# untitled.net
KiCad netlist of a schematic drawn in EAGLE
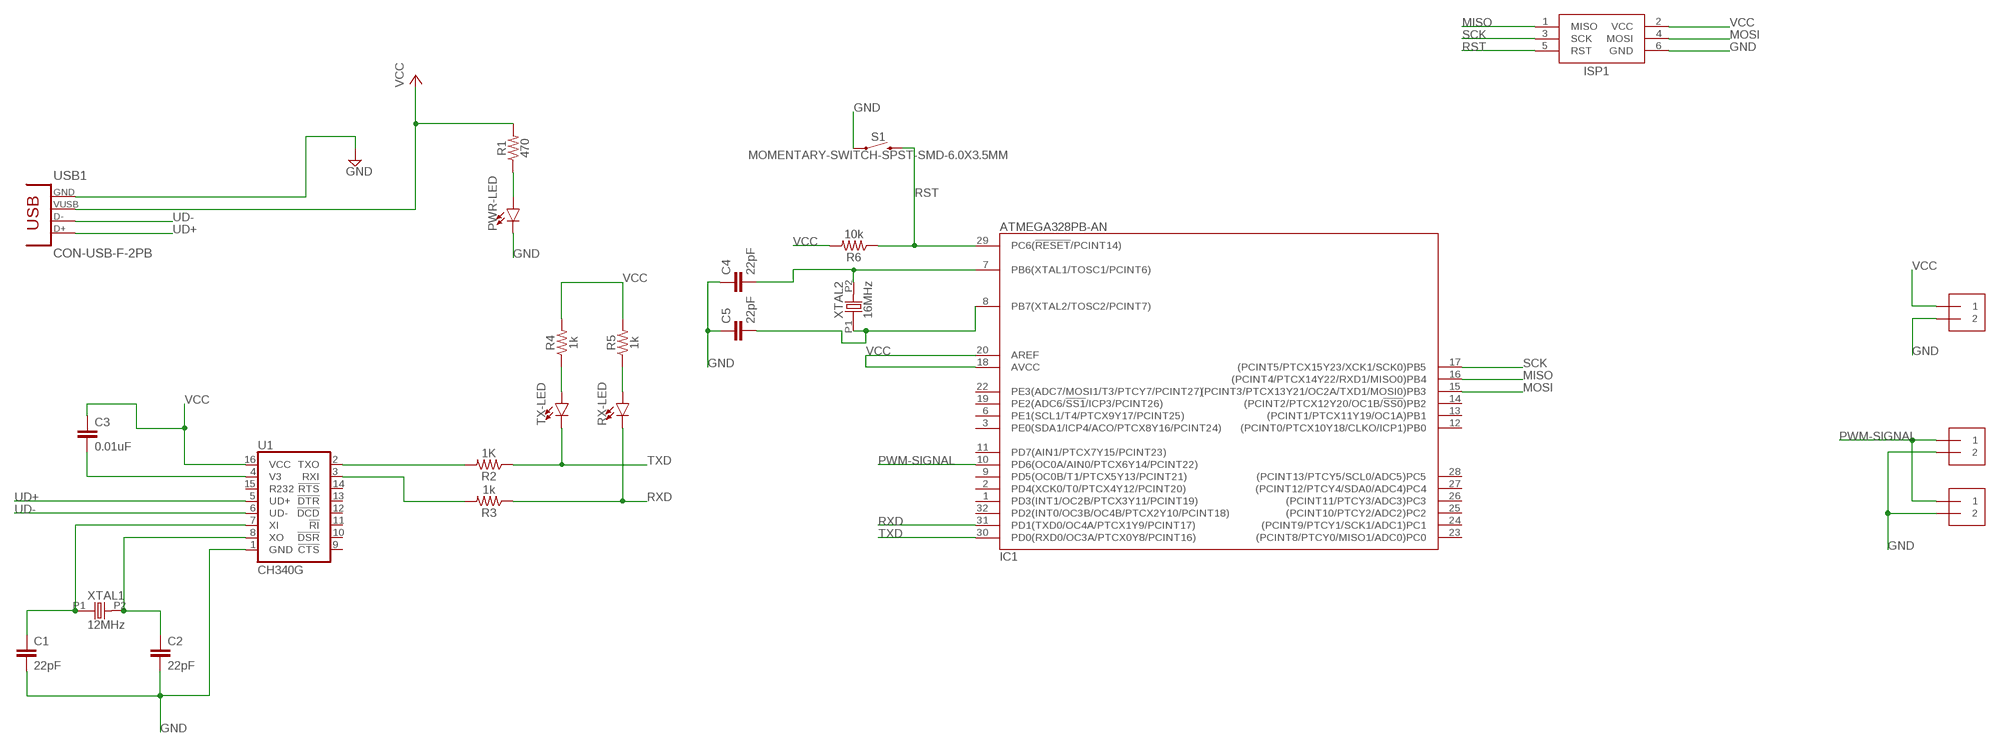
[diagram p0: schematic, sheet 1]

(export (version "E")
  (design (tool "Eeschema 10.0.6"))
  (components
    (comp (ref "5V/GND")
      (value "1X2-3.5MM")
      (footprint "eagle-import:1X2-3.5MM")
      (libsource (lib "eagle-import") (part "1X2-3.5MM"))
    )
    (comp (ref "C1")
      (value "22pF")
      (footprint "eagle-import:0603")
      (libsource (lib "eagle-import") (part "22PF-0603-50V-5%"))
    )
    (comp (ref "C2")
      (value "22pF")
      (footprint "eagle-import:0603")
      (libsource (lib "eagle-import") (part "22PF-0603-50V-5%"))
    )
    (comp (ref "C3")
      (value "0.01uF")
      (footprint "eagle-import:0603")
      (libsource (lib "eagle-import") (part "22PF-0603-50V-5%"))
    )
    (comp (ref "C4")
      (value "22pF")
      (footprint "eagle-import:0603")
      (libsource (lib "eagle-import") (part "22PF-0603-50V-5%"))
    )
    (comp (ref "C5")
      (value "22pF")
      (footprint "eagle-import:0603")
      (libsource (lib "eagle-import") (part "22PF-0603-50V-5%"))
    )
    (comp (ref "IC1")
      (value "ATMEGA328PB-AN")
      (footprint "eagle-import:QFP32_7X7_0.80")
      (libsource (lib "eagle-import") (part "ATMEGA328PB-AN"))
    )
    (comp (ref "ISP1")
      (value "AVRISP-6")
      (footprint "eagle-import:AVRISP")
      (libsource (lib "eagle-import") (part "AVRISP-6"))
    )
    (comp (ref "MOTOR-1")
      (value "1X2-3.5MM")
      (footprint "eagle-import:1X2-3.5MM")
      (libsource (lib "eagle-import") (part "1X2-3.5MM"))
    )
    (comp (ref "MOTOR-2")
      (value "1X2-3.5MM")
      (footprint "eagle-import:1X2-3.5MM")
      (libsource (lib "eagle-import") (part "1X2-3.5MM"))
    )
    (comp (ref "PWR-LED")
      (value "LED1206")
      (footprint "eagle-import:LED-1206")
      (libsource (lib "eagle-import") (part "LED1206"))
    )
    (comp (ref "R1")
      (value "470")
      (footprint "eagle-import:1206")
      (libsource (lib "eagle-import") (part "RESISTOR1206"))
    )
    (comp (ref "R2")
      (value "1K")
      (footprint "eagle-import:1206")
      (libsource (lib "eagle-import") (part "RESISTOR1206"))
    )
    (comp (ref "R3")
      (value "1k")
      (footprint "eagle-import:1206")
      (libsource (lib "eagle-import") (part "RESISTOR1206"))
    )
    (comp (ref "R4")
      (value "1k")
      (footprint "eagle-import:1206")
      (libsource (lib "eagle-import") (part "RESISTOR1206"))
    )
    (comp (ref "R5")
      (value "1k")
      (footprint "eagle-import:1206")
      (libsource (lib "eagle-import") (part "RESISTOR1206"))
    )
    (comp (ref "R6")
      (value "10k")
      (footprint "eagle-import:1206")
      (libsource (lib "eagle-import") (part "RESISTOR1206"))
    )
    (comp (ref "RX-LED")
      (value "LED1206")
      (footprint "eagle-import:LED-1206")
      (libsource (lib "eagle-import") (part "LED1206"))
    )
    (comp (ref "S1")
      (value "MOMENTARY-SWITCH-SPST-SMD-6.0X3.5MM")
      (footprint "eagle-import:TACTILE_SWITCH_SMD_6.0X3.5MM")
      (libsource (lib "eagle-import") (part "MOMENTARY-SWITCH-SPST-SMD-6.0X3.5MM"))
    )
    (comp (ref "TX-LED")
      (value "LED1206")
      (footprint "eagle-import:LED-1206")
      (libsource (lib "eagle-import") (part "LED1206"))
    )
    (comp (ref "U1")
      (value "CH340G")
      (footprint "eagle-import:SO016")
      (libsource (lib "eagle-import") (part "CH340GSMD"))
    )
    (comp (ref "USB1")
      (value "CON-USB-F-2PB")
      (footprint "eagle-import:CONN_USB_A_F")
      (libsource (lib "eagle-import") (part "CON-USB-F-2PB"))
    )
    (comp (ref "XTAL1")
      (value "12MHz")
      (footprint "eagle-import:HC-49U-PTH")
      (libsource (lib "eagle-import") (part "OSC-XTAL-HC-49U-PTH"))
    )
    (comp (ref "XTAL2")
      (value "16MHz")
      (footprint "eagle-import:HC-49U-PTH")
      (libsource (lib "eagle-import") (part "OSC-XTAL-HC-49U-PTH"))
    )
  )
  (nets
    (net (code "1") (name "/MISO") (class "Default")
      (node (ref "IC1") (pin "16") (pinfunction "(PCINT4/PTCX14Y22/RXD1/MISO0)PB4_16") (pintype "bidirectional"))
      (node (ref "ISP1") (pin "1") (pinfunction "MISO_1") (pintype "input"))
    )
    (net (code "2") (name "/MOSI") (class "Default")
      (node (ref "IC1") (pin "15") (pinfunction "(PCINT3/PTCX13Y21/OC2A/TXD1/MOSI0)PB3_15") (pintype "bidirectional"))
      (node (ref "ISP1") (pin "4") (pinfunction "MOSI_4") (pintype "output"))
    )
    (net (code "3") (name "/PWM-SIGNAL") (class "Default")
      (node (ref "IC1") (pin "10") (pinfunction "PD6(OC0A/AIN0/PTCX6Y14/PCINT22)_10") (pintype "bidirectional"))
      (node (ref "MOTOR-1") (pin "1") (pinfunction "1_1") (pintype "passive"))
      (node (ref "MOTOR-2") (pin "1") (pinfunction "1_1") (pintype "passive"))
    )
    (net (code "4") (name "/RST") (class "Default")
      (node (ref "IC1") (pin "29") (pinfunction "PC6(~{RESET}/PCINT14)_29") (pintype "bidirectional"))
      (node (ref "ISP1") (pin "5") (pinfunction "RST_5") (pintype "output"))
      (node (ref "R6") (pin "1") (pinfunction "1_1") (pintype "passive"))
      (node (ref "S1") (pin "2") (pinfunction "2_2") (pintype "passive"))
    )
    (net (code "5") (name "/RXD") (class "Default")
      (node (ref "IC1") (pin "31") (pinfunction "PD1(TXD0/OC4A/PTCX1Y9/PCINT17)_31") (pintype "bidirectional"))
      (node (ref "R3") (pin "1") (pinfunction "1_1") (pintype "passive"))
      (node (ref "RX-LED") (pin "C") (pinfunction "C_C") (pintype "passive"))
    )
    (net (code "6") (name "/SCK") (class "Default")
      (node (ref "IC1") (pin "17") (pinfunction "(PCINT5/PTCX15Y23/XCK1/SCK0)PB5_17") (pintype "bidirectional"))
      (node (ref "ISP1") (pin "3") (pinfunction "SCK_3") (pintype "output"))
    )
    (net (code "7") (name "/TXD") (class "Default")
      (node (ref "IC1") (pin "30") (pinfunction "PD0(RXD0/OC3A/PTCX0Y8/PCINT16)_30") (pintype "bidirectional"))
      (node (ref "R2") (pin "1") (pinfunction "1_1") (pintype "passive"))
      (node (ref "TX-LED") (pin "C") (pinfunction "C_C") (pintype "passive"))
    )
    (net (code "8") (name "/UD+") (class "Default")
      (node (ref "U1") (pin "5") (pinfunction "UD+_5") (pintype "bidirectional"))
      (node (ref "USB1") (pin "3") (pinfunction "D+_3") (pintype "bidirectional"))
    )
    (net (code "9") (name "/UD-") (class "Default")
      (node (ref "U1") (pin "6") (pinfunction "UD-_6") (pintype "bidirectional"))
      (node (ref "USB1") (pin "2") (pinfunction "D-_2") (pintype "bidirectional"))
    )
    (net (code "10") (name "GND") (class "Default")
      (node (ref "5V/GND") (pin "2") (pinfunction "2_2") (pintype "passive"))
      (node (ref "C1") (pin "2") (pinfunction "2_2") (pintype "passive"))
      (node (ref "C2") (pin "2") (pinfunction "2_2") (pintype "passive"))
      (node (ref "C4") (pin "1") (pinfunction "1_1") (pintype "passive"))
      (node (ref "C5") (pin "1") (pinfunction "1_1") (pintype "passive"))
      (node (ref "ISP1") (pin "6") (pinfunction "GND_6") (pintype "power_in"))
      (node (ref "MOTOR-1") (pin "2") (pinfunction "2_2") (pintype "passive"))
      (node (ref "MOTOR-2") (pin "2") (pinfunction "2_2") (pintype "passive"))
      (node (ref "PWR-LED") (pin "C") (pinfunction "C_C") (pintype "passive"))
      (node (ref "S1") (pin "1") (pinfunction "1_1") (pintype "passive"))
      (node (ref "U1") (pin "1") (pinfunction "GND_1") (pintype "bidirectional"))
      (node (ref "USB1") (pin "4") (pinfunction "GND_4") (pintype "bidirectional"))
    )
    (net (code "11") (name "Net-(IC1A-PB6(XTAL1{slash}TOSC1{slash}PCINT6))") (class "Default")
      (node (ref "C4") (pin "2") (pinfunction "2_2") (pintype "passive"))
      (node (ref "IC1") (pin "7") (pinfunction "PB6(XTAL1/TOSC1/PCINT6)_7") (pintype "bidirectional"))
      (node (ref "XTAL2") (pin "P2") (pinfunction "2_P2") (pintype "passive"))
    )
    (net (code "12") (name "Net-(IC1A-PB7(XTAL2{slash}TOSC2{slash}PCINT7))") (class "Default")
      (node (ref "C5") (pin "2") (pinfunction "2_2") (pintype "passive"))
      (node (ref "IC1") (pin "8") (pinfunction "PB7(XTAL2/TOSC2/PCINT7)_8") (pintype "bidirectional"))
      (node (ref "XTAL2") (pin "P1") (pinfunction "1_P1") (pintype "passive"))
    )
    (net (code "13") (name "Net-(PWR-LED-PadA)") (class "Default")
      (node (ref "PWR-LED") (pin "A") (pinfunction "A_A") (pintype "passive"))
      (node (ref "R1") (pin "1") (pinfunction "1_1") (pintype "passive"))
    )
    (net (code "14") (name "Net-(R4-Pad1)") (class "Default")
      (node (ref "R4") (pin "1") (pinfunction "1_1") (pintype "passive"))
      (node (ref "TX-LED") (pin "A") (pinfunction "A_A") (pintype "passive"))
    )
    (net (code "15") (name "Net-(R5-Pad1)") (class "Default")
      (node (ref "R5") (pin "1") (pinfunction "1_1") (pintype "passive"))
      (node (ref "RX-LED") (pin "A") (pinfunction "A_A") (pintype "passive"))
    )
    (net (code "16") (name "Net-(U1-RXI)") (class "Default")
      (node (ref "R3") (pin "2") (pinfunction "2_2") (pintype "passive"))
      (node (ref "U1") (pin "3") (pinfunction "RXI_3") (pintype "bidirectional"))
    )
    (net (code "17") (name "Net-(U1-TXO)") (class "Default")
      (node (ref "R2") (pin "2") (pinfunction "2_2") (pintype "passive"))
      (node (ref "U1") (pin "2") (pinfunction "TXO_2") (pintype "bidirectional"))
    )
    (net (code "18") (name "Net-(U1-V3)") (class "Default")
      (node (ref "C3") (pin "2") (pinfunction "2_2") (pintype "passive"))
      (node (ref "U1") (pin "4") (pinfunction "V3_4") (pintype "bidirectional"))
    )
    (net (code "19") (name "Net-(U1-XI)") (class "Default")
      (node (ref "C1") (pin "1") (pinfunction "1_1") (pintype "passive"))
      (node (ref "U1") (pin "7") (pinfunction "XI_7") (pintype "bidirectional"))
      (node (ref "XTAL1") (pin "P1") (pinfunction "1_P1") (pintype "passive"))
    )
    (net (code "20") (name "Net-(U1-XO)") (class "Default")
      (node (ref "C2") (pin "1") (pinfunction "1_1") (pintype "passive"))
      (node (ref "U1") (pin "8") (pinfunction "XO_8") (pintype "bidirectional"))
      (node (ref "XTAL1") (pin "P2") (pinfunction "2_P2") (pintype "passive"))
    )
    (net (code "21") (name "VCC") (class "Default")
      (node (ref "5V/GND") (pin "1") (pinfunction "1_1") (pintype "passive"))
      (node (ref "C3") (pin "1") (pinfunction "1_1") (pintype "passive"))
      (node (ref "IC1") (pin "18") (pinfunction "AVCC_18") (pintype "power_in"))
      (node (ref "IC1") (pin "20") (pinfunction "AREF_20") (pintype "passive"))
      (node (ref "ISP1") (pin "2") (pinfunction "VCC_2") (pintype "power_in"))
      (node (ref "R1") (pin "2") (pinfunction "2_2") (pintype "passive"))
      (node (ref "R4") (pin "2") (pinfunction "2_2") (pintype "passive"))
      (node (ref "R5") (pin "2") (pinfunction "2_2") (pintype "passive"))
      (node (ref "R6") (pin "2") (pinfunction "2_2") (pintype "passive"))
      (node (ref "U1") (pin "16") (pinfunction "VCC_16") (pintype "bidirectional"))
      (node (ref "USB1") (pin "1") (pinfunction "VUSB_1") (pintype "bidirectional"))
    )
    (net (code "22") (name "unconnected-(IC1A-(PCINT0{slash}PTCX10Y18{slash}CLKO{slash}ICP1)PB0-Pad12)") (class "Default")
      (node (ref "IC1") (pin "12") (pinfunction "(PCINT0/PTCX10Y18/CLKO/ICP1)PB0_12") (pintype "bidirectional"))
    )
    (net (code "23") (name "unconnected-(IC1A-(PCINT1{slash}PTCX11Y19{slash}OC1A)PB1-Pad13)") (class "Default")
      (node (ref "IC1") (pin "13") (pinfunction "(PCINT1/PTCX11Y19/OC1A)PB1_13") (pintype "bidirectional"))
    )
    (net (code "24") (name "unconnected-(IC1A-(PCINT2{slash}PTCX12Y20{slash}OC1B{slash}~{SS0})PB2-Pad14)") (class "Default")
      (node (ref "IC1") (pin "14") (pinfunction "(PCINT2/PTCX12Y20/OC1B/~{SS0})PB2_14") (pintype "bidirectional"))
    )
    (net (code "25") (name "unconnected-(IC1A-(PCINT8{slash}PTCY0{slash}MISO1{slash}ADC0)PC0-Pad23)") (class "Default")
      (node (ref "IC1") (pin "23") (pinfunction "(PCINT8/PTCY0/MISO1/ADC0)PC0_23") (pintype "bidirectional"))
    )
    (net (code "26") (name "unconnected-(IC1A-(PCINT9{slash}PTCY1{slash}SCK1{slash}ADC1)PC1-Pad24)") (class "Default")
      (node (ref "IC1") (pin "24") (pinfunction "(PCINT9/PTCY1/SCK1/ADC1)PC1_24") (pintype "bidirectional"))
    )
    (net (code "27") (name "unconnected-(IC1A-(PCINT10{slash}PTCY2{slash}ADC2)PC2-Pad25)") (class "Default")
      (node (ref "IC1") (pin "25") (pinfunction "(PCINT10/PTCY2/ADC2)PC2_25") (pintype "bidirectional"))
    )
    (net (code "28") (name "unconnected-(IC1A-(PCINT11{slash}PTCY3{slash}ADC3)PC3-Pad26)") (class "Default")
      (node (ref "IC1") (pin "26") (pinfunction "(PCINT11/PTCY3/ADC3)PC3_26") (pintype "bidirectional"))
    )
    (net (code "29") (name "unconnected-(IC1A-(PCINT12{slash}PTCY4{slash}SDA0{slash}ADC4)PC4-Pad27)") (class "Default")
      (node (ref "IC1") (pin "27") (pinfunction "(PCINT12/PTCY4/SDA0/ADC4)PC4_27") (pintype "bidirectional"))
    )
    (net (code "30") (name "unconnected-(IC1A-(PCINT13{slash}PTCY5{slash}SCL0{slash}ADC5)PC5-Pad28)") (class "Default")
      (node (ref "IC1") (pin "28") (pinfunction "(PCINT13/PTCY5/SCL0/ADC5)PC5_28") (pintype "bidirectional"))
    )
    (net (code "31") (name "unconnected-(IC1A-PD2(INT0{slash}OC3B{slash}OC4B{slash}PTCX2Y10{slash}PCINT18)-Pad32)") (class "Default")
      (node (ref "IC1") (pin "32") (pinfunction "PD2(INT0/OC3B/OC4B/PTCX2Y10/PCINT18)_32") (pintype "bidirectional"))
    )
    (net (code "32") (name "unconnected-(IC1A-PD3(INT1{slash}OC2B{slash}PTCX3Y11{slash}PCINT19)-Pad1)") (class "Default")
      (node (ref "IC1") (pin "1") (pinfunction "PD3(INT1/OC2B/PTCX3Y11/PCINT19)_1") (pintype "bidirectional"))
    )
    (net (code "33") (name "unconnected-(IC1A-PD4(XCK0{slash}T0{slash}PTCX4Y12{slash}PCINT20)-Pad2)") (class "Default")
      (node (ref "IC1") (pin "2") (pinfunction "PD4(XCK0/T0/PTCX4Y12/PCINT20)_2") (pintype "bidirectional"))
    )
    (net (code "34") (name "unconnected-(IC1A-PD5(OC0B{slash}T1{slash}PTCX5Y13{slash}PCINT21)-Pad9)") (class "Default")
      (node (ref "IC1") (pin "9") (pinfunction "PD5(OC0B/T1/PTCX5Y13/PCINT21)_9") (pintype "bidirectional"))
    )
    (net (code "35") (name "unconnected-(IC1A-PD7(AIN1{slash}PTCX7Y15{slash}PCINT23)-Pad11)") (class "Default")
      (node (ref "IC1") (pin "11") (pinfunction "PD7(AIN1/PTCX7Y15/PCINT23)_11") (pintype "bidirectional"))
    )
    (net (code "36") (name "unconnected-(IC1A-PE0(SDA1{slash}ICP4{slash}ACO{slash}PTCX8Y16{slash}PCINT24)-Pad3)") (class "Default")
      (node (ref "IC1") (pin "3") (pinfunction "PE0(SDA1/ICP4/ACO/PTCX8Y16/PCINT24)_3") (pintype "bidirectional"))
    )
    (net (code "37") (name "unconnected-(IC1A-PE1(SCL1{slash}T4{slash}PTCX9Y17{slash}PCINT25)-Pad6)") (class "Default")
      (node (ref "IC1") (pin "6") (pinfunction "PE1(SCL1/T4/PTCX9Y17/PCINT25)_6") (pintype "bidirectional"))
    )
    (net (code "38") (name "unconnected-(IC1A-PE2(ADC6{slash}~{SS1}{slash}ICP3{slash}PCINT26)-Pad19)") (class "Default")
      (node (ref "IC1") (pin "19") (pinfunction "PE2(ADC6/~{SS1}/ICP3/PCINT26)_19") (pintype "bidirectional"))
    )
    (net (code "39") (name "unconnected-(IC1A-PE3(ADC7{slash}MOSI1{slash}T3{slash}PTCY7{slash}PCINT27)-Pad22)") (class "Default")
      (node (ref "IC1") (pin "22") (pinfunction "PE3(ADC7/MOSI1/T3/PTCY7/PCINT27)_22") (pintype "bidirectional"))
    )
    (net (code "40") (name "unconnected-(U1-R232-Pad15)") (class "Default")
      (node (ref "U1") (pin "15") (pinfunction "R232_15") (pintype "bidirectional"))
    )
    (net (code "41") (name "unconnected-(U1-~{CTS}-Pad9)") (class "Default")
      (node (ref "U1") (pin "9") (pinfunction "~{CTS}_9") (pintype "bidirectional"))
    )
    (net (code "42") (name "unconnected-(U1-~{DCD}-Pad12)") (class "Default")
      (node (ref "U1") (pin "12") (pinfunction "~{DCD}_12") (pintype "bidirectional"))
    )
    (net (code "43") (name "unconnected-(U1-~{DSR}-Pad10)") (class "Default")
      (node (ref "U1") (pin "10") (pinfunction "~{DSR}_10") (pintype "bidirectional"))
    )
    (net (code "44") (name "unconnected-(U1-~{DTR}-Pad13)") (class "Default")
      (node (ref "U1") (pin "13") (pinfunction "~{DTR}_13") (pintype "bidirectional"))
    )
    (net (code "45") (name "unconnected-(U1-~{RI}-Pad11)") (class "Default")
      (node (ref "U1") (pin "11") (pinfunction "~{RI}_11") (pintype "bidirectional"))
    )
    (net (code "46") (name "unconnected-(U1-~{RTS}-Pad14)") (class "Default")
      (node (ref "U1") (pin "14") (pinfunction "~{RTS}_14") (pintype "bidirectional"))
    )
  )
)
